# automaton.net
KiCad netlist of a schematic drawn in EAGLE
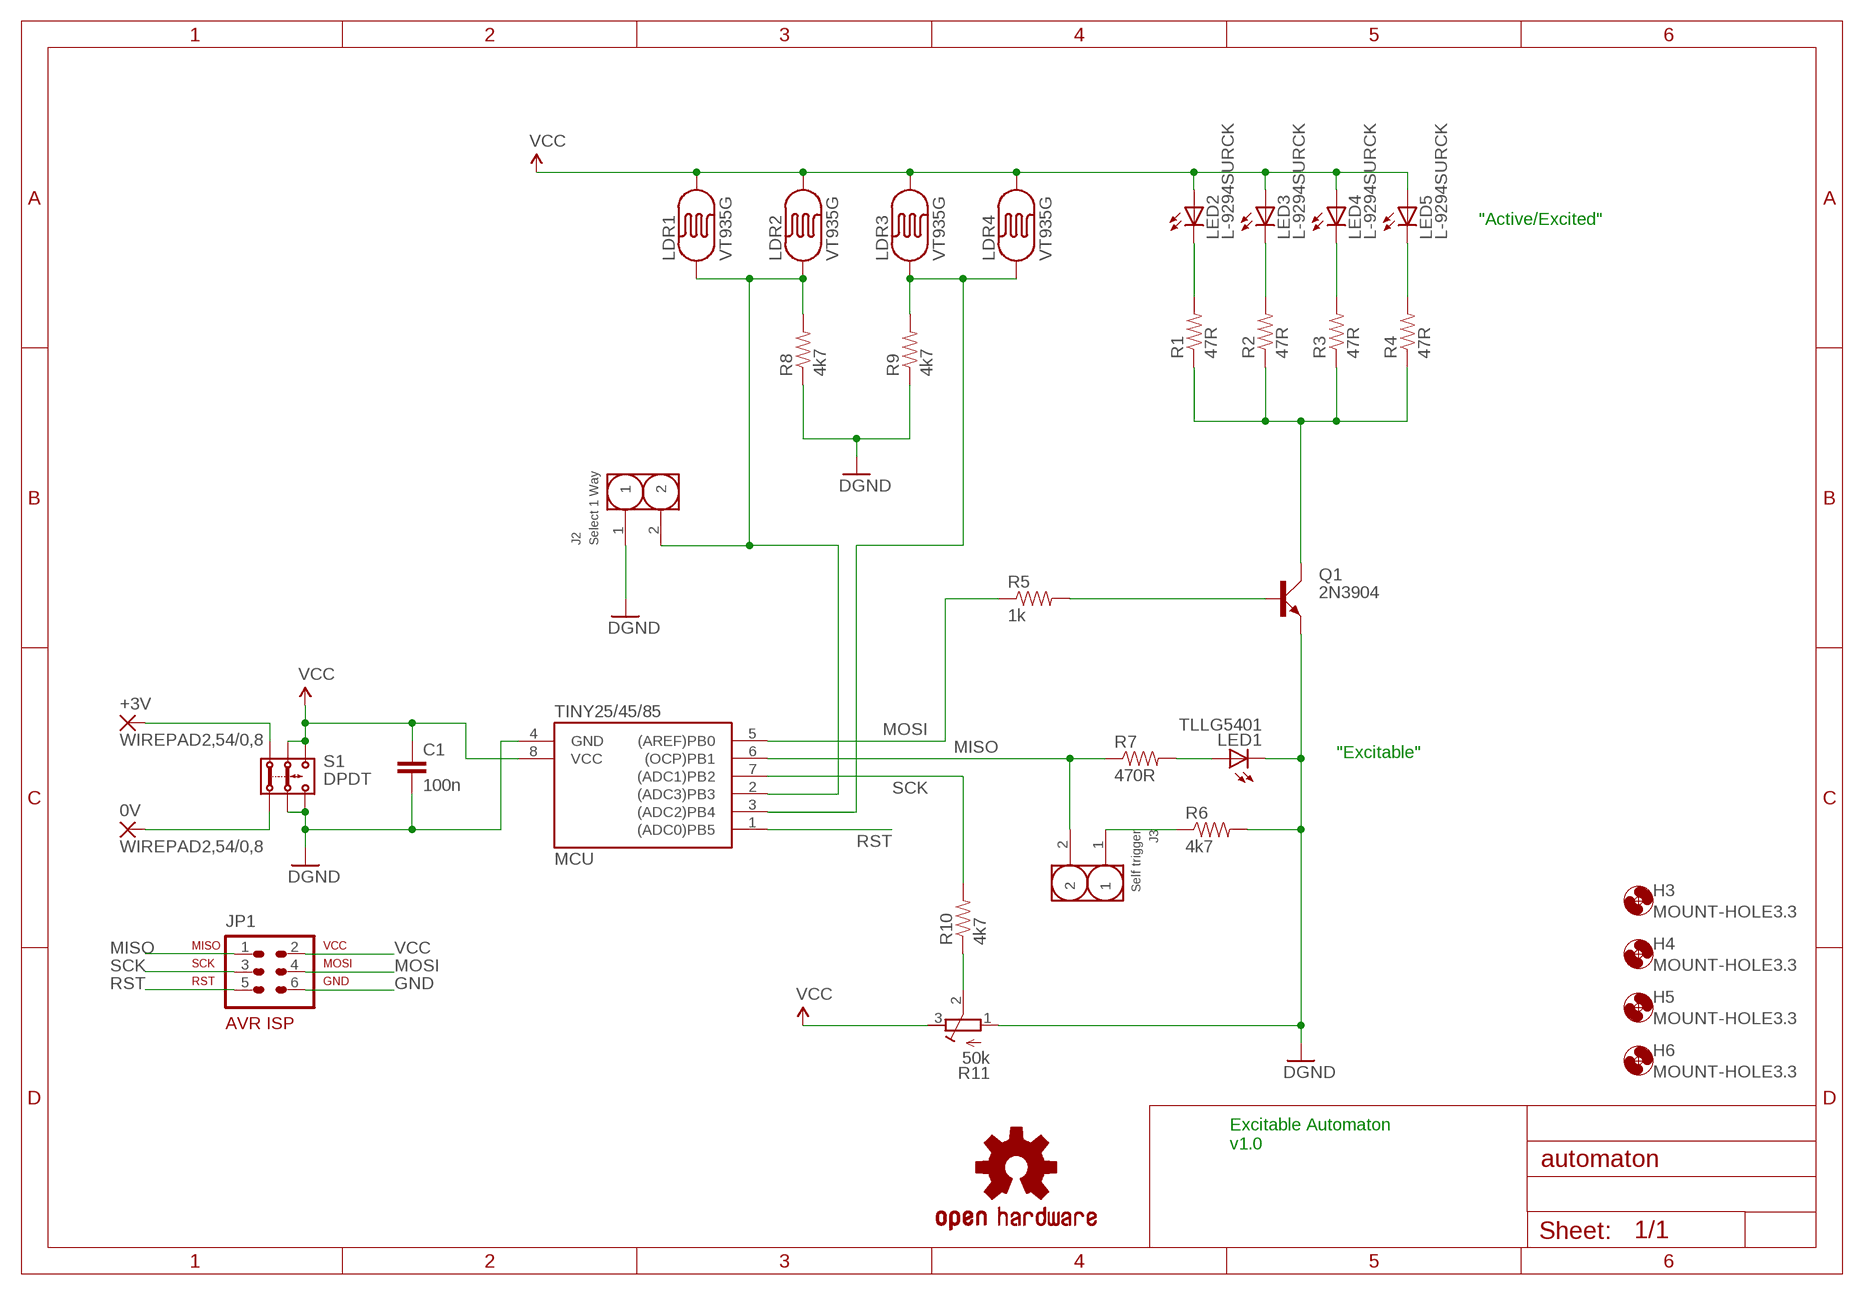
[diagram p0: schematic, sheet 1]

(export (version "E")
  (design (tool "Eeschema 10.0.6"))
  (components
    (comp (ref "+3V")
      (value "WIREPAD2,54/0,8")
      (footprint "eagle-import:2,54_0,8")
      (libsource (lib "eagle-import") (part "WIREPAD2,54/0,8"))
    )
    (comp (ref "0V")
      (value "WIREPAD2,54/0,8")
      (footprint "eagle-import:2,54_0,8")
      (libsource (lib "eagle-import") (part "WIREPAD2,54/0,8"))
    )
    (comp (ref "C1")
      (value "100n")
      (footprint "eagle-import:C10B4")
      (libsource (lib "eagle-import") (part "C10/4"))
    )
    (comp (ref "H3")
      (value "MOUNT-HOLE3.3")
      (footprint "eagle-import:3,3")
      (libsource (lib "eagle-import") (part "MOUNT-HOLE3.3"))
    )
    (comp (ref "H4")
      (value "MOUNT-HOLE3.3")
      (footprint "eagle-import:3,3")
      (libsource (lib "eagle-import") (part "MOUNT-HOLE3.3"))
    )
    (comp (ref "H5")
      (value "MOUNT-HOLE3.3")
      (footprint "eagle-import:3,3")
      (libsource (lib "eagle-import") (part "MOUNT-HOLE3.3"))
    )
    (comp (ref "H6")
      (value "MOUNT-HOLE3.3")
      (footprint "eagle-import:3,3")
      (libsource (lib "eagle-import") (part "MOUNT-HOLE3.3"))
    )
    (comp (ref "J2")
      (value "Select 1 Way")
      (footprint "eagle-import:2P-2.54")
      (libsource (lib "eagle-import") (part "HEADER-2P-2.54"))
    )
    (comp (ref "J3")
      (value "Self trigger")
      (footprint "eagle-import:2P-2.54")
      (libsource (lib "eagle-import") (part "HEADER-2P-2.54"))
    )
    (comp (ref "JP1")
      (value "AVR-ISP-6VERT")
      (footprint "eagle-import:AVR-ISP-6")
      (libsource (lib "eagle-import") (part "AVR-ISP-6VERT"))
    )
    (comp (ref "LDR1")
      (value "VT935G")
      (footprint "eagle-import:PHOTOCELL")
      (libsource (lib "eagle-import") (part "PHOTOCELLPTH"))
    )
    (comp (ref "LDR2")
      (value "VT935G")
      (footprint "eagle-import:PHOTOCELL")
      (libsource (lib "eagle-import") (part "PHOTOCELLPTH"))
    )
    (comp (ref "LDR3")
      (value "VT935G")
      (footprint "eagle-import:PHOTOCELL")
      (libsource (lib "eagle-import") (part "PHOTOCELLPTH"))
    )
    (comp (ref "LDR4")
      (value "VT935G")
      (footprint "eagle-import:PHOTOCELL")
      (libsource (lib "eagle-import") (part "PHOTOCELLPTH"))
    )
    (comp (ref "LED1")
      (value "TLLG5401")
      (footprint "eagle-import:LED5MM")
      (libsource (lib "eagle-import") (part "LED5MM"))
    )
    (comp (ref "LED2")
      (value "L-9294SURCK")
      (footprint "eagle-import:LED5MM")
      (libsource (lib "eagle-import") (part "LED5MM"))
    )
    (comp (ref "LED3")
      (value "L-9294SURCK")
      (footprint "eagle-import:LED5MM")
      (libsource (lib "eagle-import") (part "LED5MM"))
    )
    (comp (ref "LED4")
      (value "L-9294SURCK")
      (footprint "eagle-import:LED5MM")
      (libsource (lib "eagle-import") (part "LED5MM"))
    )
    (comp (ref "LED5")
      (value "L-9294SURCK")
      (footprint "eagle-import:LED5MM")
      (libsource (lib "eagle-import") (part "LED5MM"))
    )
    (comp (ref "LOGO1")
      (value "OSHW-LOGOS")
      (footprint "eagle-import:OSHW-LOGO-S")
      (libsource (lib "eagle-import") (part "OSHW-LOGOS"))
    )
    (comp (ref "MCU")
      (value "TINY25/45/85")
      (footprint "eagle-import:DIL08")
      (libsource (lib "eagle-import") (part "TINY25/45/85"))
    )
    (comp (ref "Q1")
      (value "2N3904")
      (footprint "eagle-import:TO92D")
      (libsource (lib "eagle-import") (part "2N3904"))
    )
    (comp (ref "R1")
      (value "47R")
      (footprint "eagle-import:AXIAL-0.3")
      (libsource (lib "eagle-import") (part "RESISTORAXIAL-0.3"))
    )
    (comp (ref "R2")
      (value "47R")
      (footprint "eagle-import:AXIAL-0.3")
      (libsource (lib "eagle-import") (part "RESISTORAXIAL-0.3"))
    )
    (comp (ref "R3")
      (value "47R")
      (footprint "eagle-import:AXIAL-0.3")
      (libsource (lib "eagle-import") (part "RESISTORAXIAL-0.3"))
    )
    (comp (ref "R4")
      (value "47R")
      (footprint "eagle-import:AXIAL-0.3")
      (libsource (lib "eagle-import") (part "RESISTORAXIAL-0.3"))
    )
    (comp (ref "R5")
      (value "1k")
      (footprint "eagle-import:AXIAL-0.3")
      (libsource (lib "eagle-import") (part "RESISTORAXIAL-0.3"))
    )
    (comp (ref "R6")
      (value "4k7")
      (footprint "eagle-import:AXIAL-0.3")
      (libsource (lib "eagle-import") (part "RESISTORAXIAL-0.3"))
    )
    (comp (ref "R7")
      (value "470R")
      (footprint "eagle-import:AXIAL-0.3")
      (libsource (lib "eagle-import") (part "RESISTORAXIAL-0.3"))
    )
    (comp (ref "R8")
      (value "4k7")
      (footprint "eagle-import:AXIAL-0.3")
      (libsource (lib "eagle-import") (part "RESISTORAXIAL-0.3"))
    )
    (comp (ref "R9")
      (value "4k7")
      (footprint "eagle-import:AXIAL-0.3")
      (libsource (lib "eagle-import") (part "RESISTORAXIAL-0.3"))
    )
    (comp (ref "R10")
      (value "4k7")
      (footprint "eagle-import:AXIAL-0.3")
      (libsource (lib "eagle-import") (part "RESISTORAXIAL-0.3"))
    )
    (comp (ref "R11")
      (value "50k")
      (footprint "eagle-import:RTRIM3296Y")
      (libsource (lib "eagle-import") (part "R-TRIMM3296Y"))
    )
    (comp (ref "S1")
      (value "DPDT")
      (footprint "eagle-import:2P2T")
      (libsource (lib "eagle-import") (part "2P2T"))
    )
  )
  (nets
    (net (code "1") (name "/MISO") (class "Default")
      (node (ref "J3") (pin "2") (pinfunction "2_2") (pintype "bidirectional"))
      (node (ref "JP1") (pin "1") (pinfunction "1_1") (pintype "passive"))
      (node (ref "MCU") (pin "6") (pinfunction "(OCP)PB1_6") (pintype "bidirectional"))
      (node (ref "R7") (pin "P$1") (pinfunction "1_P$1") (pintype "passive"))
    )
    (net (code "2") (name "/MOSI") (class "Default")
      (node (ref "JP1") (pin "4") (pinfunction "4_4") (pintype "passive"))
      (node (ref "MCU") (pin "5") (pinfunction "(AREF)PB0_5") (pintype "bidirectional"))
      (node (ref "R5") (pin "P$1") (pinfunction "1_P$1") (pintype "passive"))
    )
    (net (code "3") (name "/RST") (class "Default")
      (node (ref "JP1") (pin "5") (pinfunction "5_5") (pintype "passive"))
      (node (ref "MCU") (pin "1") (pinfunction "(ADC0)PB5_1") (pintype "bidirectional"))
    )
    (net (code "4") (name "/SCK") (class "Default")
      (node (ref "JP1") (pin "3") (pinfunction "3_3") (pintype "passive"))
      (node (ref "MCU") (pin "7") (pinfunction "(ADC1)PB2_7") (pintype "bidirectional"))
      (node (ref "R10") (pin "P$2") (pinfunction "2_P$2") (pintype "passive"))
    )
    (net (code "5") (name "DGND") (class "Default")
      (node (ref "C1") (pin "2") (pinfunction "2_2") (pintype "passive"))
      (node (ref "J2") (pin "1") (pinfunction "1_1") (pintype "bidirectional"))
      (node (ref "JP1") (pin "6") (pinfunction "6_6") (pintype "passive"))
      (node (ref "LED1") (pin "K") (pinfunction "C_K") (pintype "passive"))
      (node (ref "MCU") (pin "4") (pinfunction "GND_4") (pintype "power_in"))
      (node (ref "Q1") (pin "E") (pinfunction "E_E") (pintype "passive"))
      (node (ref "R11") (pin "1") (pinfunction "E_1") (pintype "passive"))
      (node (ref "R6") (pin "P$2") (pinfunction "2_P$2") (pintype "passive"))
      (node (ref "R8") (pin "P$1") (pinfunction "1_P$1") (pintype "passive"))
      (node (ref "R9") (pin "P$1") (pinfunction "1_P$1") (pintype "passive"))
      (node (ref "S1") (pin "2.2") (pinfunction "2.2_2.2") (pintype "passive"))
      (node (ref "S1") (pin "3.2") (pinfunction "3.2_3.2") (pintype "passive"))
    )
    (net (code "6") (name "Net-(+3V-P)") (class "Default")
      (node (ref "+3V") (pin "1") (pinfunction "P_1") (pintype "passive"))
      (node (ref "S1") (pin "1.1") (pinfunction "1.1_1.1") (pintype "passive"))
    )
    (net (code "7") (name "Net-(0V-P)") (class "Default")
      (node (ref "0V") (pin "1") (pinfunction "P_1") (pintype "passive"))
      (node (ref "S1") (pin "1.2") (pinfunction "1.2_1.2") (pintype "passive"))
    )
    (net (code "8") (name "Net-(LDR1-P$1)") (class "Default")
      (node (ref "J2") (pin "2") (pinfunction "2_2") (pintype "bidirectional"))
      (node (ref "LDR1") (pin "1") (pinfunction "P$1_1") (pintype "bidirectional"))
      (node (ref "LDR2") (pin "1") (pinfunction "P$1_1") (pintype "bidirectional"))
      (node (ref "MCU") (pin "2") (pinfunction "(ADC3)PB3_2") (pintype "bidirectional"))
      (node (ref "R8") (pin "P$2") (pinfunction "2_P$2") (pintype "passive"))
    )
    (net (code "9") (name "Net-(LDR3-P$1)") (class "Default")
      (node (ref "LDR3") (pin "1") (pinfunction "P$1_1") (pintype "bidirectional"))
      (node (ref "LDR4") (pin "1") (pinfunction "P$1_1") (pintype "bidirectional"))
      (node (ref "MCU") (pin "3") (pinfunction "(ADC2)PB4_3") (pintype "bidirectional"))
      (node (ref "R9") (pin "P$2") (pinfunction "2_P$2") (pintype "passive"))
    )
    (net (code "10") (name "Net-(LED2-C)") (class "Default")
      (node (ref "LED2") (pin "K") (pinfunction "C_K") (pintype "passive"))
      (node (ref "R1") (pin "P$2") (pinfunction "2_P$2") (pintype "passive"))
    )
    (net (code "11") (name "Net-(LED3-C)") (class "Default")
      (node (ref "LED3") (pin "K") (pinfunction "C_K") (pintype "passive"))
      (node (ref "R2") (pin "P$2") (pinfunction "2_P$2") (pintype "passive"))
    )
    (net (code "12") (name "Net-(LED4-C)") (class "Default")
      (node (ref "LED4") (pin "K") (pinfunction "C_K") (pintype "passive"))
      (node (ref "R3") (pin "P$2") (pinfunction "2_P$2") (pintype "passive"))
    )
    (net (code "13") (name "Net-(LED5-C)") (class "Default")
      (node (ref "LED5") (pin "K") (pinfunction "C_K") (pintype "passive"))
      (node (ref "R4") (pin "P$2") (pinfunction "2_P$2") (pintype "passive"))
    )
    (net (code "14") (name "Net-(R1-1)") (class "Default")
      (node (ref "Q1") (pin "C") (pinfunction "C_C") (pintype "passive"))
      (node (ref "R1") (pin "P$1") (pinfunction "1_P$1") (pintype "passive"))
      (node (ref "R2") (pin "P$1") (pinfunction "1_P$1") (pintype "passive"))
      (node (ref "R3") (pin "P$1") (pinfunction "1_P$1") (pintype "passive"))
      (node (ref "R4") (pin "P$1") (pinfunction "1_P$1") (pintype "passive"))
    )
    (net (code "15") (name "Net-(R5-2)") (class "Default")
      (node (ref "Q1") (pin "B") (pinfunction "B_B") (pintype "passive"))
      (node (ref "R5") (pin "P$2") (pinfunction "2_P$2") (pintype "passive"))
    )
    (net (code "16") (name "Net-(R6-1)") (class "Default")
      (node (ref "J3") (pin "1") (pinfunction "1_1") (pintype "bidirectional"))
      (node (ref "R6") (pin "P$1") (pinfunction "1_P$1") (pintype "passive"))
    )
    (net (code "17") (name "Net-(R7-2)") (class "Default")
      (node (ref "LED1") (pin "A") (pinfunction "A_A") (pintype "passive"))
      (node (ref "R7") (pin "P$2") (pinfunction "2_P$2") (pintype "passive"))
    )
    (net (code "18") (name "Net-(R10-1)") (class "Default")
      (node (ref "R10") (pin "P$1") (pinfunction "1_P$1") (pintype "passive"))
      (node (ref "R11") (pin "2") (pinfunction "S_2") (pintype "passive"))
    )
    (net (code "19") (name "VCC") (class "Default")
      (node (ref "C1") (pin "1") (pinfunction "1_1") (pintype "passive"))
      (node (ref "JP1") (pin "2") (pinfunction "2_2") (pintype "passive"))
      (node (ref "LDR1") (pin "2") (pinfunction "P$2_2") (pintype "bidirectional"))
      (node (ref "LDR2") (pin "2") (pinfunction "P$2_2") (pintype "bidirectional"))
      (node (ref "LDR3") (pin "2") (pinfunction "P$2_2") (pintype "bidirectional"))
      (node (ref "LDR4") (pin "2") (pinfunction "P$2_2") (pintype "bidirectional"))
      (node (ref "LED2") (pin "A") (pinfunction "A_A") (pintype "passive"))
      (node (ref "LED3") (pin "A") (pinfunction "A_A") (pintype "passive"))
      (node (ref "LED4") (pin "A") (pinfunction "A_A") (pintype "passive"))
      (node (ref "LED5") (pin "A") (pinfunction "A_A") (pintype "passive"))
      (node (ref "MCU") (pin "8") (pinfunction "VCC_8") (pintype "power_in"))
      (node (ref "R11") (pin "3") (pinfunction "A_3") (pintype "passive"))
      (node (ref "S1") (pin "2.1") (pinfunction "2.1_2.1") (pintype "passive"))
      (node (ref "S1") (pin "3.1") (pinfunction "3.1_3.1") (pintype "passive"))
    )
  )
)
